# Controller_Peripheral_Iso.net
KiCad netlist of a schematic drawn in Altium Designer
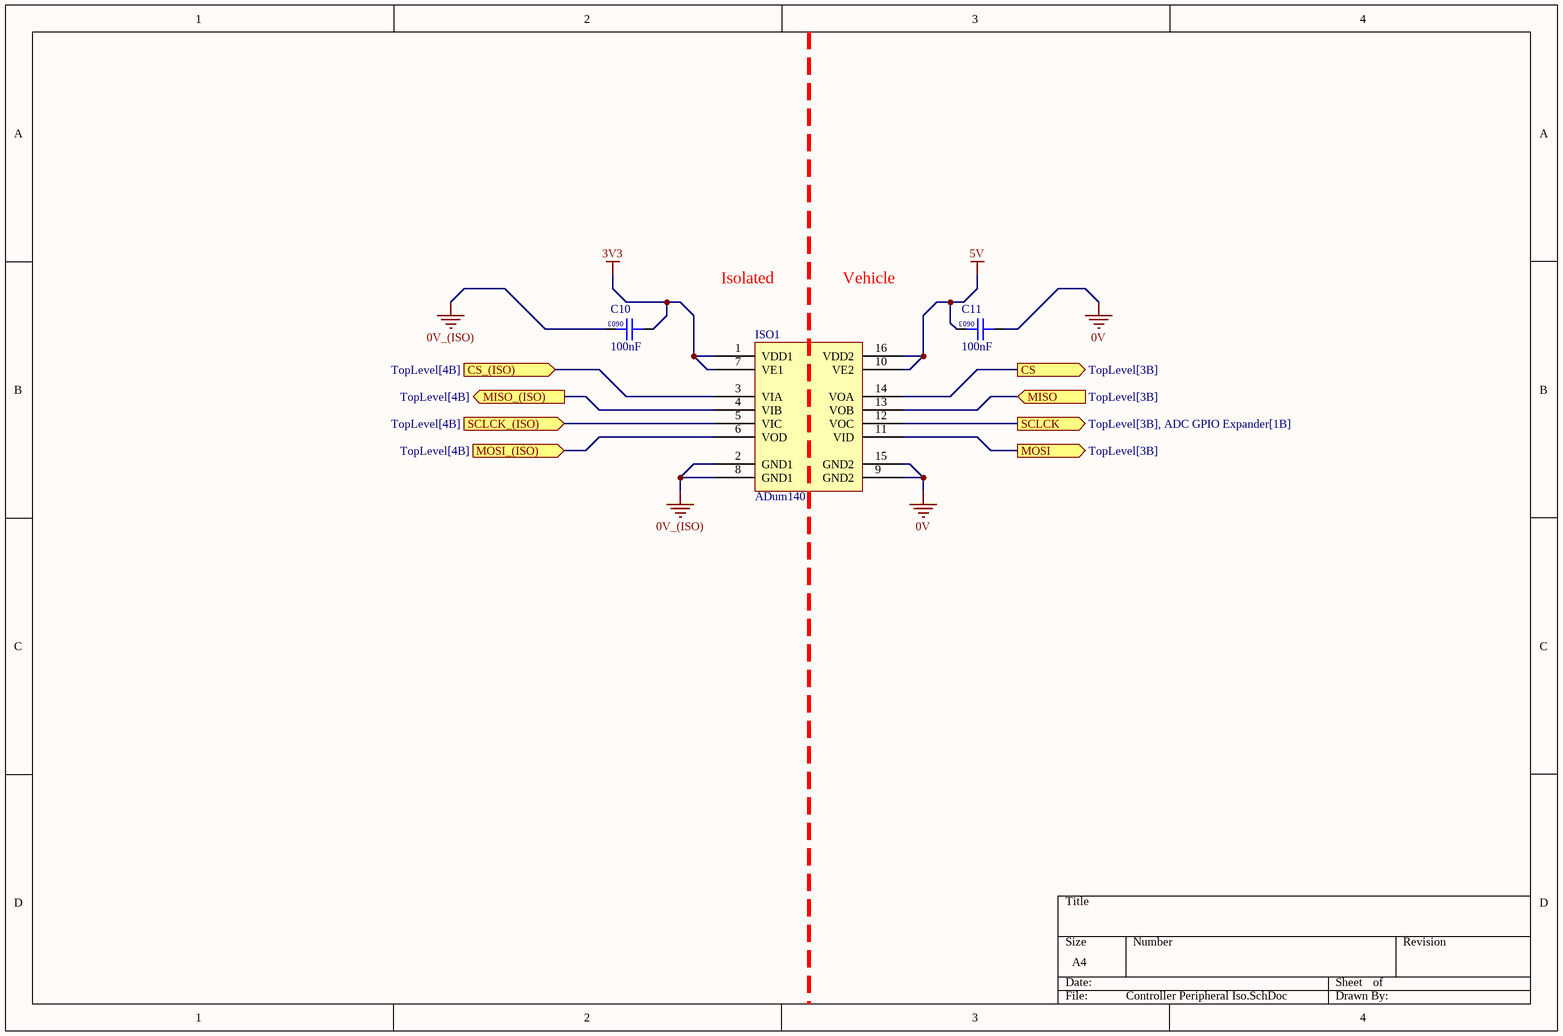
[diagram p0: Controller Peripheral Iso.SchDoc]

(export (version "E")
  (design (tool "Eeschema 10.0.6"))
  (components
    (comp (ref "C10")
      (value "100nF")
      (footprint "0603")
      (fields
        (field (name "PART NUMBER") "GCM188L81H104KA57D")
        (field (name "MANUFACTURER") "muRata")
        (field (name "TOLERANCE") "±10%")
      )
      (libsource (lib "ts_standard_library") (part "Capacitor 0603"))
    )
    (comp (ref "C11")
      (value "100nF")
      (footprint "0603")
      (fields
        (field (name "PART NUMBER") "GCM188L81H104KA57D")
        (field (name "MANUFACTURER") "muRata")
        (field (name "TOLERANCE") "±10%")
      )
      (libsource (lib "ts_standard_library") (part "Capacitor 0603"))
    )
    (comp (ref "ISO1")
      (value "ADum1401")
      (footprint "AD 16-SOIC")
      (fields (field (name "PART NUMBER") "ADuM1401") (field (name "MANUFACTURER") "Analog Devices"))
      (libsource (lib "ts_standard_library") (part "ADum1401"))
    )
  )
  (nets
    (net (code "1") (name "/CS") (class "Default")
      (node (ref "ISO1") (pin "14") (pinfunction "VOA_14") (pintype "passive"))
    )
    (net (code "2") (name "/CS_(ISO)") (class "Default")
      (node (ref "ISO1") (pin "3") (pinfunction "VIA_3") (pintype "passive"))
    )
    (net (code "3") (name "/MISO") (class "Default")
      (node (ref "ISO1") (pin "13") (pinfunction "VOB_13") (pintype "passive"))
    )
    (net (code "4") (name "/MISO_(ISO)") (class "Default")
      (node (ref "ISO1") (pin "4") (pinfunction "VIB_4") (pintype "passive"))
    )
    (net (code "5") (name "/MOSI") (class "Default")
      (node (ref "ISO1") (pin "11") (pinfunction "VID_11") (pintype "passive"))
    )
    (net (code "6") (name "/MOSI_(ISO)") (class "Default")
      (node (ref "ISO1") (pin "6") (pinfunction "VOD_6") (pintype "passive"))
    )
    (net (code "7") (name "/SCLCK") (class "Default")
      (node (ref "ISO1") (pin "12") (pinfunction "VOC_12") (pintype "passive"))
    )
    (net (code "8") (name "/SCLCK_(ISO)") (class "Default")
      (node (ref "ISO1") (pin "5") (pinfunction "VIC_5") (pintype "passive"))
    )
    (net (code "9") (name "0V") (class "Default")
      (node (ref "C11") (pin "1") (pinfunction "1_1") (pintype "passive"))
      (node (ref "ISO1") (pin "15") (pinfunction "GND2_15") (pintype "passive"))
      (node (ref "ISO1") (pin "9") (pinfunction "GND2_9") (pintype "passive"))
    )
    (net (code "10") (name "0V_(ISO)") (class "Default")
      (node (ref "C10") (pin "2") (pinfunction "2_2") (pintype "passive"))
      (node (ref "ISO1") (pin "2") (pinfunction "GND1_2") (pintype "passive"))
      (node (ref "ISO1") (pin "8") (pinfunction "GND1_8") (pintype "passive"))
    )
    (net (code "11") (name "3V3") (class "Default")
      (node (ref "C10") (pin "1") (pinfunction "1_1") (pintype "passive"))
      (node (ref "ISO1") (pin "1") (pinfunction "VDD1_1") (pintype "passive"))
      (node (ref "ISO1") (pin "7") (pinfunction "VE1_7") (pintype "passive"))
    )
    (net (code "12") (name "5V") (class "Default")
      (node (ref "C11") (pin "2") (pinfunction "2_2") (pintype "passive"))
      (node (ref "ISO1") (pin "10") (pinfunction "VE2_10") (pintype "passive"))
      (node (ref "ISO1") (pin "16") (pinfunction "VDD2_16") (pintype "passive"))
    )
  )
)
